# RasPi7021.net
KiCad netlist of a schematic drawn in EAGLE
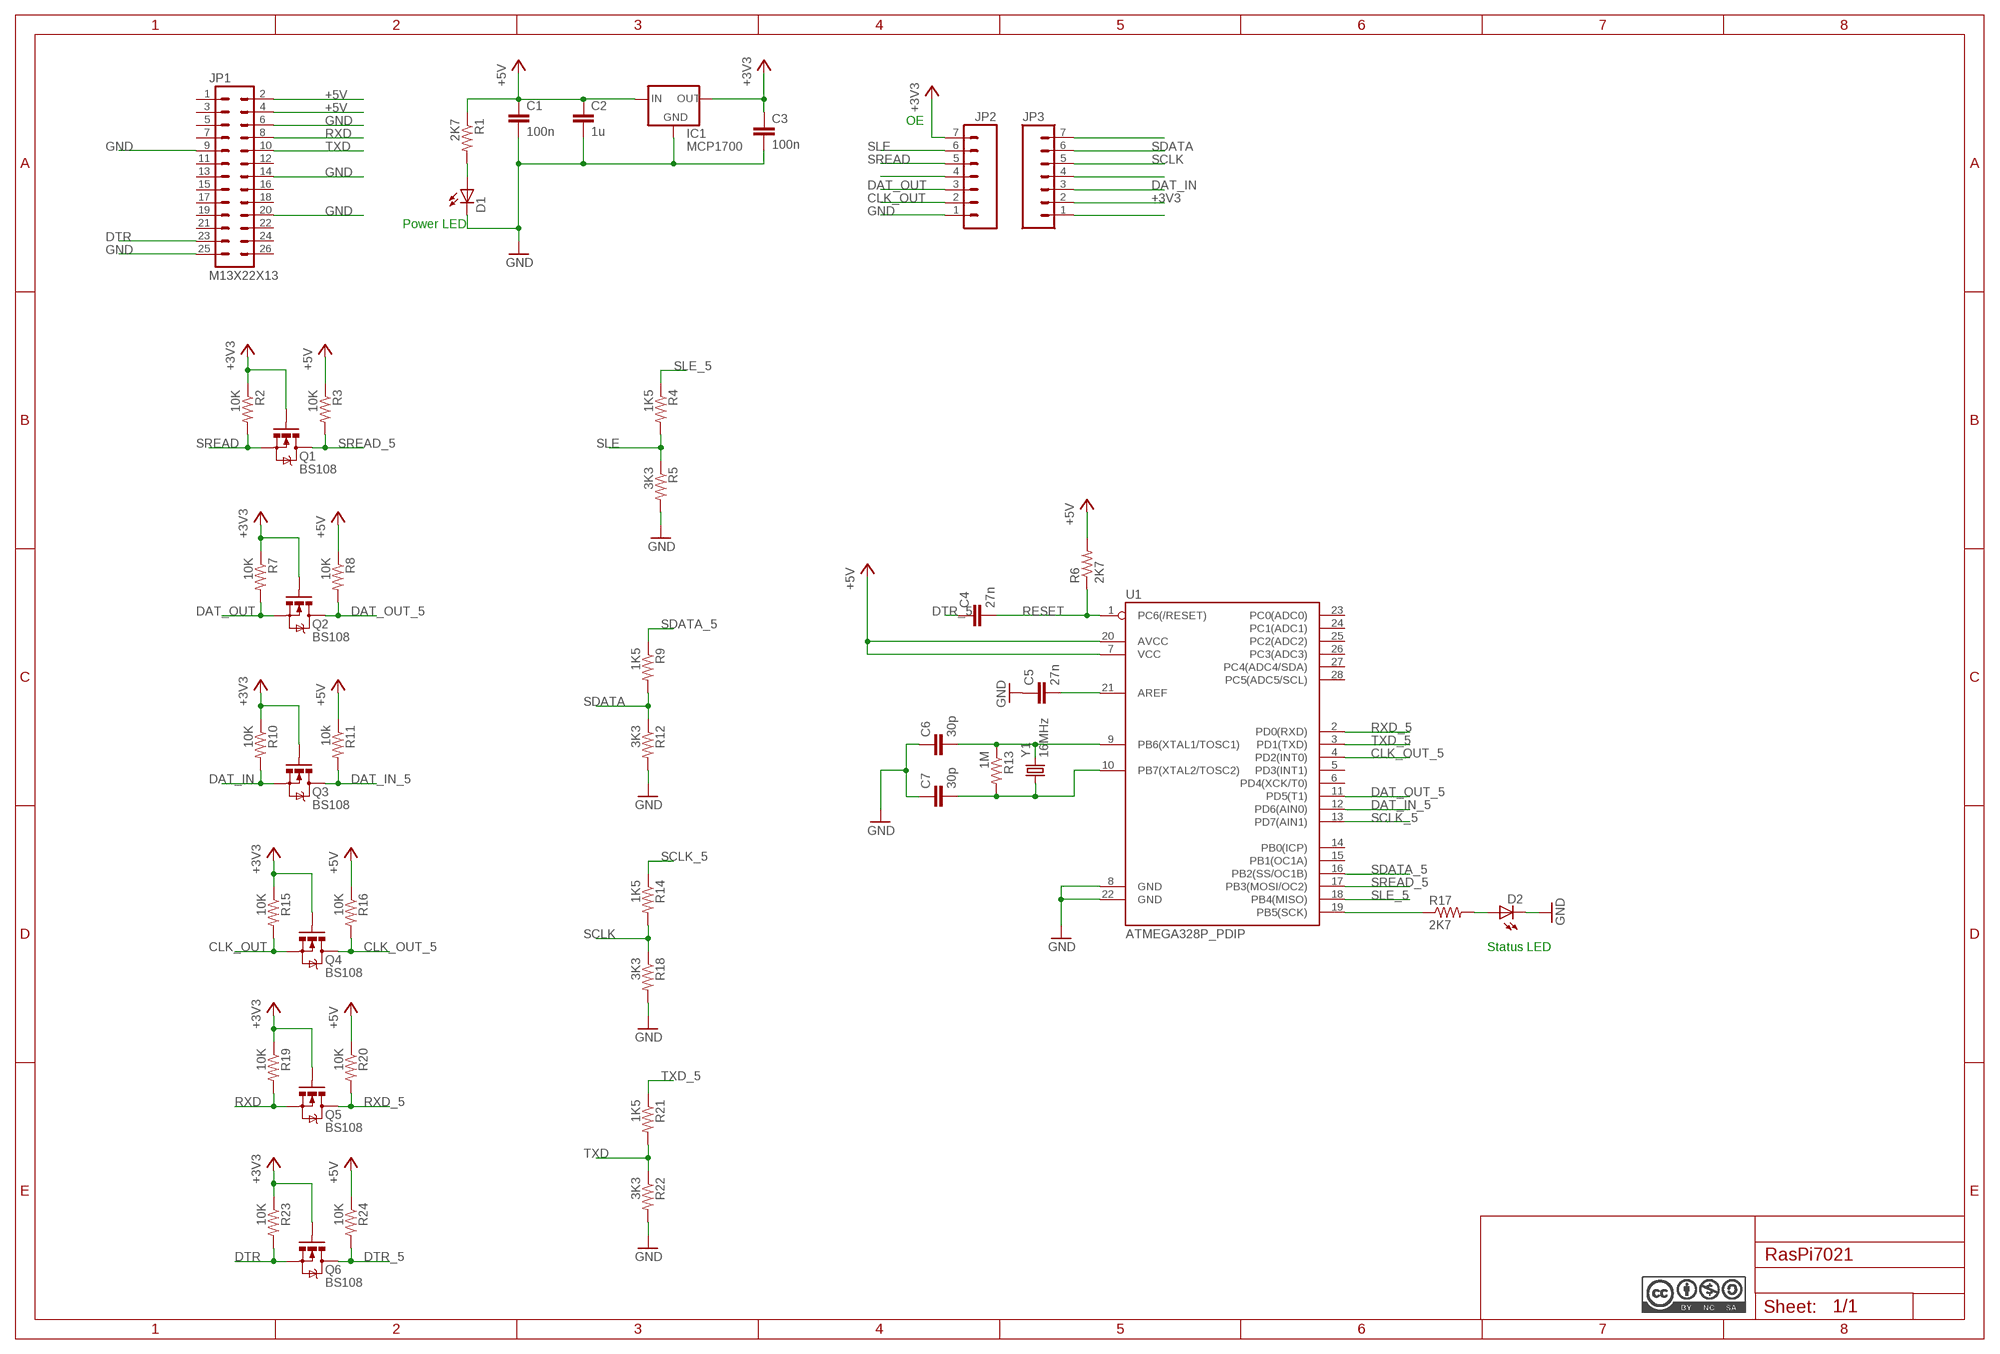
[diagram p0: schematic, sheet 1]

(export (version "E")
  (design (tool "Eeschema 10.0.6"))
  (components
    (comp (ref "C1")
      (value "100n")
      (footprint "eagle-import:CAP-PTH-SMALLEZ")
      (libsource (lib "eagle-import") (part "CAPEZ"))
    )
    (comp (ref "C2")
      (value "1u")
      (footprint "eagle-import:CAP-PTH-SMALLEZ")
      (libsource (lib "eagle-import") (part "CAPEZ"))
    )
    (comp (ref "C3")
      (value "100n")
      (footprint "eagle-import:CAP-PTH-SMALLEZ")
      (libsource (lib "eagle-import") (part "CAPEZ"))
    )
    (comp (ref "C4")
      (value "27n")
      (footprint "eagle-import:CAP-PTH-SMALLEZ")
      (libsource (lib "eagle-import") (part "CAPEZ"))
    )
    (comp (ref "C5")
      (value "27n")
      (footprint "eagle-import:CAP-PTH-SMALLEZ")
      (libsource (lib "eagle-import") (part "CAPEZ"))
    )
    (comp (ref "C6")
      (value "30p")
      (footprint "eagle-import:CAP-PTH-SMALLEZ")
      (libsource (lib "eagle-import") (part "CAPEZ"))
    )
    (comp (ref "C7")
      (value "30p")
      (footprint "eagle-import:CAP-PTH-SMALLEZ")
      (libsource (lib "eagle-import") (part "CAPEZ"))
    )
    (comp (ref "D1")
      (value "LED3MM")
      (footprint "eagle-import:LED3MM")
      (libsource (lib "eagle-import") (part "LED3MM"))
    )
    (comp (ref "D2")
      (value "LED3MM")
      (footprint "eagle-import:LED3MM")
      (libsource (lib "eagle-import") (part "LED3MM"))
    )
    (comp (ref "IC1")
      (value "MCP1700")
      (footprint "eagle-import:TO92-INLINE")
      (libsource (lib "eagle-import") (part "MCP1700INLINE"))
    )
    (comp (ref "JP1")
      (value "M13X22X13")
      (footprint "eagle-import:2X13")
      (libsource (lib "eagle-import") (part "M13X22X13"))
    )
    (comp (ref "JP2")
      (value "M07")
      (footprint "eagle-import:1X07")
      (libsource (lib "eagle-import") (part "M07"))
    )
    (comp (ref "JP3")
      (value "M07")
      (footprint "eagle-import:1X07")
      (libsource (lib "eagle-import") (part "M07"))
    )
    (comp (ref "Q1")
      (value "BS108")
      (footprint "eagle-import:TO-92")
      (libsource (lib "eagle-import") (part "MOSFET-NCHANNELBS170"))
    )
    (comp (ref "Q2")
      (value "BS108")
      (footprint "eagle-import:TO-92")
      (libsource (lib "eagle-import") (part "MOSFET-NCHANNELBS170"))
    )
    (comp (ref "Q3")
      (value "BS108")
      (footprint "eagle-import:TO-92")
      (libsource (lib "eagle-import") (part "MOSFET-NCHANNELBS170"))
    )
    (comp (ref "Q4")
      (value "BS108")
      (footprint "eagle-import:TO-92")
      (libsource (lib "eagle-import") (part "MOSFET-NCHANNELBS170"))
    )
    (comp (ref "Q5")
      (value "BS108")
      (footprint "eagle-import:TO-92")
      (libsource (lib "eagle-import") (part "MOSFET-NCHANNELBS170"))
    )
    (comp (ref "Q6")
      (value "BS108")
      (footprint "eagle-import:TO-92")
      (libsource (lib "eagle-import") (part "MOSFET-NCHANNELBS170"))
    )
    (comp (ref "R1")
      (value "2K7")
      (footprint "eagle-import:AXIAL-0.3EZ")
      (libsource (lib "eagle-import") (part "RESISTOREZ"))
    )
    (comp (ref "R2")
      (value "10K")
      (footprint "eagle-import:AXIAL-0.3EZ")
      (libsource (lib "eagle-import") (part "RESISTOREZ"))
    )
    (comp (ref "R3")
      (value "10K")
      (footprint "eagle-import:AXIAL-0.3EZ")
      (libsource (lib "eagle-import") (part "RESISTOREZ"))
    )
    (comp (ref "R4")
      (value "1K5")
      (footprint "eagle-import:AXIAL-0.3EZ")
      (libsource (lib "eagle-import") (part "RESISTOREZ"))
    )
    (comp (ref "R5")
      (value "3K3")
      (footprint "eagle-import:AXIAL-0.3EZ")
      (libsource (lib "eagle-import") (part "RESISTOREZ"))
    )
    (comp (ref "R6")
      (value "2K7")
      (footprint "eagle-import:AXIAL-0.3EZ")
      (libsource (lib "eagle-import") (part "RESISTOREZ"))
    )
    (comp (ref "R7")
      (value "10K")
      (footprint "eagle-import:AXIAL-0.3EZ")
      (libsource (lib "eagle-import") (part "RESISTOREZ"))
    )
    (comp (ref "R8")
      (value "10K")
      (footprint "eagle-import:AXIAL-0.3EZ")
      (libsource (lib "eagle-import") (part "RESISTOREZ"))
    )
    (comp (ref "R9")
      (value "1K5")
      (footprint "eagle-import:AXIAL-0.3EZ")
      (libsource (lib "eagle-import") (part "RESISTOREZ"))
    )
    (comp (ref "R10")
      (value "10K")
      (footprint "eagle-import:AXIAL-0.3EZ")
      (libsource (lib "eagle-import") (part "RESISTOREZ"))
    )
    (comp (ref "R11")
      (value "10k")
      (footprint "eagle-import:AXIAL-0.3EZ")
      (libsource (lib "eagle-import") (part "RESISTOREZ"))
    )
    (comp (ref "R12")
      (value "3K3")
      (footprint "eagle-import:AXIAL-0.3EZ")
      (libsource (lib "eagle-import") (part "RESISTOREZ"))
    )
    (comp (ref "R13")
      (value "1M")
      (footprint "eagle-import:AXIAL-0.3EZ")
      (libsource (lib "eagle-import") (part "RESISTOREZ"))
    )
    (comp (ref "R14")
      (value "1K5")
      (footprint "eagle-import:AXIAL-0.3EZ")
      (libsource (lib "eagle-import") (part "RESISTOREZ"))
    )
    (comp (ref "R15")
      (value "10K")
      (footprint "eagle-import:AXIAL-0.3EZ")
      (libsource (lib "eagle-import") (part "RESISTOREZ"))
    )
    (comp (ref "R16")
      (value "10K")
      (footprint "eagle-import:AXIAL-0.3EZ")
      (libsource (lib "eagle-import") (part "RESISTOREZ"))
    )
    (comp (ref "R17")
      (value "2K7")
      (footprint "eagle-import:AXIAL-0.3EZ")
      (libsource (lib "eagle-import") (part "RESISTOREZ"))
    )
    (comp (ref "R18")
      (value "3K3")
      (footprint "eagle-import:AXIAL-0.3EZ")
      (libsource (lib "eagle-import") (part "RESISTOREZ"))
    )
    (comp (ref "R19")
      (value "10K")
      (footprint "eagle-import:AXIAL-0.3EZ")
      (libsource (lib "eagle-import") (part "RESISTOREZ"))
    )
    (comp (ref "R20")
      (value "10K")
      (footprint "eagle-import:AXIAL-0.3EZ")
      (libsource (lib "eagle-import") (part "RESISTOREZ"))
    )
    (comp (ref "R21")
      (value "1K5")
      (footprint "eagle-import:AXIAL-0.3EZ")
      (libsource (lib "eagle-import") (part "RESISTOREZ"))
    )
    (comp (ref "R22")
      (value "3K3")
      (footprint "eagle-import:AXIAL-0.3EZ")
      (libsource (lib "eagle-import") (part "RESISTOREZ"))
    )
    (comp (ref "R23")
      (value "10K")
      (footprint "eagle-import:AXIAL-0.3EZ")
      (libsource (lib "eagle-import") (part "RESISTOREZ"))
    )
    (comp (ref "R24")
      (value "10K")
      (footprint "eagle-import:AXIAL-0.3EZ")
      (libsource (lib "eagle-import") (part "RESISTOREZ"))
    )
    (comp (ref "U1")
      (value "ATMEGA328P_PDIP")
      (footprint "eagle-import:DIL28-3")
      (libsource (lib "eagle-import") (part "ATMEGA328P_PDIP"))
    )
    (comp (ref "Y1")
      (value "16MHz")
      (footprint "eagle-import:CRYSTAL_HC49_S")
      (libsource (lib "eagle-import") (part "CRYSTAL_CRYSTALHC49S"))
    )
  )
  (nets
    (net (code "1") (name "+3V3") (class "Default")
      (node (ref "C3") (pin "1") (pinfunction "1_1") (pintype "passive"))
      (node (ref "IC1") (pin "3") (pinfunction "OUT_3") (pintype "passive"))
      (node (ref "JP2") (pin "7") (pinfunction "7_7") (pintype "passive"))
      (node (ref "JP3") (pin "2") (pinfunction "2_2") (pintype "passive"))
      (node (ref "Q1") (pin "2") (pinfunction "G_2") (pintype "passive"))
      (node (ref "Q2") (pin "2") (pinfunction "G_2") (pintype "passive"))
      (node (ref "Q3") (pin "2") (pinfunction "G_2") (pintype "passive"))
      (node (ref "Q4") (pin "2") (pinfunction "G_2") (pintype "passive"))
      (node (ref "Q5") (pin "2") (pinfunction "G_2") (pintype "passive"))
      (node (ref "Q6") (pin "2") (pinfunction "G_2") (pintype "passive"))
      (node (ref "R10") (pin "P$1") (pinfunction "1_P$1") (pintype "passive"))
      (node (ref "R15") (pin "P$1") (pinfunction "1_P$1") (pintype "passive"))
      (node (ref "R19") (pin "P$1") (pinfunction "1_P$1") (pintype "passive"))
      (node (ref "R2") (pin "P$1") (pinfunction "1_P$1") (pintype "passive"))
      (node (ref "R23") (pin "P$1") (pinfunction "1_P$1") (pintype "passive"))
      (node (ref "R7") (pin "P$1") (pinfunction "1_P$1") (pintype "passive"))
    )
    (net (code "2") (name "+5V") (class "Default")
      (node (ref "C1") (pin "1") (pinfunction "1_1") (pintype "passive"))
      (node (ref "C2") (pin "1") (pinfunction "1_1") (pintype "passive"))
      (node (ref "IC1") (pin "2") (pinfunction "IN_2") (pintype "input"))
      (node (ref "JP1") (pin "2") (pinfunction "2_2") (pintype "passive"))
      (node (ref "JP1") (pin "4") (pinfunction "4_4") (pintype "passive"))
      (node (ref "R1") (pin "P$1") (pinfunction "1_P$1") (pintype "passive"))
      (node (ref "R11") (pin "P$1") (pinfunction "1_P$1") (pintype "passive"))
      (node (ref "R16") (pin "P$1") (pinfunction "1_P$1") (pintype "passive"))
      (node (ref "R20") (pin "P$1") (pinfunction "1_P$1") (pintype "passive"))
      (node (ref "R24") (pin "P$1") (pinfunction "1_P$1") (pintype "passive"))
      (node (ref "R3") (pin "P$1") (pinfunction "1_P$1") (pintype "passive"))
      (node (ref "R6") (pin "P$2") (pinfunction "2_P$2") (pintype "passive"))
      (node (ref "R8") (pin "P$1") (pinfunction "1_P$1") (pintype "passive"))
      (node (ref "U1") (pin "20") (pinfunction "AVCC_20") (pintype "bidirectional"))
      (node (ref "U1") (pin "7") (pinfunction "VCC_7") (pintype "bidirectional"))
    )
    (net (code "3") (name "/CLK_OUT") (class "Default")
      (node (ref "JP2") (pin "2") (pinfunction "2_2") (pintype "passive"))
      (node (ref "Q4") (pin "3") (pinfunction "S_3") (pintype "passive"))
      (node (ref "R15") (pin "P$2") (pinfunction "2_P$2") (pintype "passive"))
    )
    (net (code "4") (name "/CLK_OUT_5") (class "Default")
      (node (ref "Q4") (pin "1") (pinfunction "D_1") (pintype "passive"))
      (node (ref "R16") (pin "P$2") (pinfunction "2_P$2") (pintype "passive"))
      (node (ref "U1") (pin "4") (pinfunction "PD2(INT0)_4") (pintype "bidirectional"))
    )
    (net (code "5") (name "/DAT_IN") (class "Default")
      (node (ref "JP3") (pin "3") (pinfunction "3_3") (pintype "passive"))
      (node (ref "Q3") (pin "3") (pinfunction "S_3") (pintype "passive"))
      (node (ref "R10") (pin "P$2") (pinfunction "2_P$2") (pintype "passive"))
    )
    (net (code "6") (name "/DAT_IN_5") (class "Default")
      (node (ref "Q3") (pin "1") (pinfunction "D_1") (pintype "passive"))
      (node (ref "R11") (pin "P$2") (pinfunction "2_P$2") (pintype "passive"))
      (node (ref "U1") (pin "12") (pinfunction "PD6(AIN0)_12") (pintype "bidirectional"))
    )
    (net (code "7") (name "/DAT_OUT") (class "Default")
      (node (ref "JP2") (pin "3") (pinfunction "3_3") (pintype "passive"))
      (node (ref "Q2") (pin "3") (pinfunction "S_3") (pintype "passive"))
      (node (ref "R7") (pin "P$2") (pinfunction "2_P$2") (pintype "passive"))
    )
    (net (code "8") (name "/DAT_OUT_5") (class "Default")
      (node (ref "Q2") (pin "1") (pinfunction "D_1") (pintype "passive"))
      (node (ref "R8") (pin "P$2") (pinfunction "2_P$2") (pintype "passive"))
      (node (ref "U1") (pin "11") (pinfunction "PD5(T1)_11") (pintype "bidirectional"))
    )
    (net (code "9") (name "/DTR") (class "Default")
      (node (ref "JP1") (pin "23") (pinfunction "23_23") (pintype "passive"))
      (node (ref "Q6") (pin "3") (pinfunction "S_3") (pintype "passive"))
      (node (ref "R23") (pin "P$2") (pinfunction "2_P$2") (pintype "passive"))
    )
    (net (code "10") (name "/DTR_5") (class "Default")
      (node (ref "C4") (pin "1") (pinfunction "1_1") (pintype "passive"))
      (node (ref "Q6") (pin "1") (pinfunction "D_1") (pintype "passive"))
      (node (ref "R24") (pin "P$2") (pinfunction "2_P$2") (pintype "passive"))
    )
    (net (code "11") (name "/RESET") (class "Default")
      (node (ref "C4") (pin "2") (pinfunction "2_2") (pintype "passive"))
      (node (ref "R6") (pin "P$1") (pinfunction "1_P$1") (pintype "passive"))
      (node (ref "U1") (pin "1") (pinfunction "PC6(/RESET)_1") (pintype "bidirectional"))
    )
    (net (code "12") (name "/RXD") (class "Default")
      (node (ref "JP1") (pin "8") (pinfunction "8_8") (pintype "passive"))
      (node (ref "Q5") (pin "3") (pinfunction "S_3") (pintype "passive"))
      (node (ref "R19") (pin "P$2") (pinfunction "2_P$2") (pintype "passive"))
    )
    (net (code "13") (name "/RXD_5") (class "Default")
      (node (ref "Q5") (pin "1") (pinfunction "D_1") (pintype "passive"))
      (node (ref "R20") (pin "P$2") (pinfunction "2_P$2") (pintype "passive"))
      (node (ref "U1") (pin "2") (pinfunction "PD0(RXD)_2") (pintype "bidirectional"))
    )
    (net (code "14") (name "/SCLK") (class "Default")
      (node (ref "JP3") (pin "5") (pinfunction "5_5") (pintype "passive"))
      (node (ref "R14") (pin "P$2") (pinfunction "2_P$2") (pintype "passive"))
      (node (ref "R18") (pin "P$1") (pinfunction "1_P$1") (pintype "passive"))
    )
    (net (code "15") (name "/SCLK_5") (class "Default")
      (node (ref "R14") (pin "P$1") (pinfunction "1_P$1") (pintype "passive"))
      (node (ref "U1") (pin "13") (pinfunction "PD7(AIN1)_13") (pintype "bidirectional"))
    )
    (net (code "16") (name "/SDATA") (class "Default")
      (node (ref "JP3") (pin "6") (pinfunction "6_6") (pintype "passive"))
      (node (ref "R12") (pin "P$1") (pinfunction "1_P$1") (pintype "passive"))
      (node (ref "R9") (pin "P$2") (pinfunction "2_P$2") (pintype "passive"))
    )
    (net (code "17") (name "/SDATA_5") (class "Default")
      (node (ref "R9") (pin "P$1") (pinfunction "1_P$1") (pintype "passive"))
      (node (ref "U1") (pin "16") (pinfunction "PB2(SS/OC1B)_16") (pintype "bidirectional"))
    )
    (net (code "18") (name "/SLE") (class "Default")
      (node (ref "JP2") (pin "6") (pinfunction "6_6") (pintype "passive"))
      (node (ref "R4") (pin "P$2") (pinfunction "2_P$2") (pintype "passive"))
      (node (ref "R5") (pin "P$1") (pinfunction "1_P$1") (pintype "passive"))
    )
    (net (code "19") (name "/SLE_5") (class "Default")
      (node (ref "R4") (pin "P$1") (pinfunction "1_P$1") (pintype "passive"))
      (node (ref "U1") (pin "18") (pinfunction "PB4(MISO)_18") (pintype "bidirectional"))
    )
    (net (code "20") (name "/SREAD") (class "Default")
      (node (ref "JP2") (pin "5") (pinfunction "5_5") (pintype "passive"))
      (node (ref "Q1") (pin "3") (pinfunction "S_3") (pintype "passive"))
      (node (ref "R2") (pin "P$2") (pinfunction "2_P$2") (pintype "passive"))
    )
    (net (code "21") (name "/SREAD_5") (class "Default")
      (node (ref "Q1") (pin "1") (pinfunction "D_1") (pintype "passive"))
      (node (ref "R3") (pin "P$2") (pinfunction "2_P$2") (pintype "passive"))
      (node (ref "U1") (pin "17") (pinfunction "PB3(MOSI/OC2)_17") (pintype "bidirectional"))
    )
    (net (code "22") (name "/TXD") (class "Default")
      (node (ref "JP1") (pin "10") (pinfunction "10_10") (pintype "passive"))
      (node (ref "R21") (pin "P$2") (pinfunction "2_P$2") (pintype "passive"))
      (node (ref "R22") (pin "P$1") (pinfunction "1_P$1") (pintype "passive"))
    )
    (net (code "23") (name "/TXD_5") (class "Default")
      (node (ref "R21") (pin "P$1") (pinfunction "1_P$1") (pintype "passive"))
      (node (ref "U1") (pin "3") (pinfunction "PD1(TXD)_3") (pintype "bidirectional"))
    )
    (net (code "24") (name "GND") (class "Default")
      (node (ref "C1") (pin "2") (pinfunction "2_2") (pintype "passive"))
      (node (ref "C2") (pin "2") (pinfunction "2_2") (pintype "passive"))
      (node (ref "C3") (pin "2") (pinfunction "2_2") (pintype "passive"))
      (node (ref "C5") (pin "1") (pinfunction "1_1") (pintype "passive"))
      (node (ref "C6") (pin "1") (pinfunction "1_1") (pintype "passive"))
      (node (ref "C7") (pin "1") (pinfunction "1_1") (pintype "passive"))
      (node (ref "D1") (pin "K") (pinfunction "C_K") (pintype "passive"))
      (node (ref "D2") (pin "K") (pinfunction "C_K") (pintype "passive"))
      (node (ref "IC1") (pin "1") (pinfunction "GND_1") (pintype "input"))
      (node (ref "JP1") (pin "14") (pinfunction "14_14") (pintype "passive"))
      (node (ref "JP1") (pin "20") (pinfunction "20_20") (pintype "passive"))
      (node (ref "JP1") (pin "25") (pinfunction "25_25") (pintype "passive"))
      (node (ref "JP1") (pin "6") (pinfunction "6_6") (pintype "passive"))
      (node (ref "JP1") (pin "9") (pinfunction "9_9") (pintype "passive"))
      (node (ref "JP2") (pin "1") (pinfunction "1_1") (pintype "passive"))
      (node (ref "R12") (pin "P$2") (pinfunction "2_P$2") (pintype "passive"))
      (node (ref "R18") (pin "P$2") (pinfunction "2_P$2") (pintype "passive"))
      (node (ref "R22") (pin "P$2") (pinfunction "2_P$2") (pintype "passive"))
      (node (ref "R5") (pin "P$2") (pinfunction "2_P$2") (pintype "passive"))
      (node (ref "U1") (pin "22") (pinfunction "GND_22") (pintype "bidirectional"))
      (node (ref "U1") (pin "8") (pinfunction "GND_8") (pintype "bidirectional"))
    )
    (net (code "25") (name "Net-(R1-2)") (class "Default")
      (node (ref "D1") (pin "A") (pinfunction "A_A") (pintype "passive"))
      (node (ref "R1") (pin "P$2") (pinfunction "2_P$2") (pintype "passive"))
    )
    (net (code "26") (name "Net-(R13-1)") (class "Default")
      (node (ref "C6") (pin "2") (pinfunction "2_2") (pintype "passive"))
      (node (ref "R13") (pin "P$1") (pinfunction "1_P$1") (pintype "passive"))
      (node (ref "U1") (pin "9") (pinfunction "PB6(XTAL1/TOSC1)_9") (pintype "bidirectional"))
      (node (ref "Y1") (pin "2") (pinfunction "2_2") (pintype "passive"))
    )
    (net (code "27") (name "Net-(R13-2)") (class "Default")
      (node (ref "C7") (pin "2") (pinfunction "2_2") (pintype "passive"))
      (node (ref "R13") (pin "P$2") (pinfunction "2_P$2") (pintype "passive"))
      (node (ref "U1") (pin "10") (pinfunction "PB7(XTAL2/TOSC2)_10") (pintype "bidirectional"))
      (node (ref "Y1") (pin "1") (pinfunction "1_1") (pintype "passive"))
    )
    (net (code "28") (name "Net-(R17-1)") (class "Default")
      (node (ref "R17") (pin "P$1") (pinfunction "1_P$1") (pintype "passive"))
      (node (ref "U1") (pin "19") (pinfunction "PB5(SCK)_19") (pintype "bidirectional"))
    )
    (net (code "29") (name "Net-(R17-2)") (class "Default")
      (node (ref "D2") (pin "A") (pinfunction "A_A") (pintype "passive"))
      (node (ref "R17") (pin "P$2") (pinfunction "2_P$2") (pintype "passive"))
    )
    (net (code "30") (name "Net-(U1-AREF)") (class "Default")
      (node (ref "C5") (pin "2") (pinfunction "2_2") (pintype "passive"))
      (node (ref "U1") (pin "21") (pinfunction "AREF_21") (pintype "bidirectional"))
    )
    (net (code "31") (name "unconnected-(JP1-Pad1)") (class "Default")
      (node (ref "JP1") (pin "1") (pinfunction "1_1") (pintype "passive"))
    )
    (net (code "32") (name "unconnected-(JP1-Pad3)") (class "Default")
      (node (ref "JP1") (pin "3") (pinfunction "3_3") (pintype "passive"))
    )
    (net (code "33") (name "unconnected-(JP1-Pad5)") (class "Default")
      (node (ref "JP1") (pin "5") (pinfunction "5_5") (pintype "passive"))
    )
    (net (code "34") (name "unconnected-(JP1-Pad7)") (class "Default")
      (node (ref "JP1") (pin "7") (pinfunction "7_7") (pintype "passive"))
    )
    (net (code "35") (name "unconnected-(JP1-Pad11)") (class "Default")
      (node (ref "JP1") (pin "11") (pinfunction "11_11") (pintype "passive"))
    )
    (net (code "36") (name "unconnected-(JP1-Pad12)") (class "Default")
      (node (ref "JP1") (pin "12") (pinfunction "12_12") (pintype "passive"))
    )
    (net (code "37") (name "unconnected-(JP1-Pad13)") (class "Default")
      (node (ref "JP1") (pin "13") (pinfunction "13_13") (pintype "passive"))
    )
    (net (code "38") (name "unconnected-(JP1-Pad15)") (class "Default")
      (node (ref "JP1") (pin "15") (pinfunction "15_15") (pintype "passive"))
    )
    (net (code "39") (name "unconnected-(JP1-Pad16)") (class "Default")
      (node (ref "JP1") (pin "16") (pinfunction "16_16") (pintype "passive"))
    )
    (net (code "40") (name "unconnected-(JP1-Pad17)") (class "Default")
      (node (ref "JP1") (pin "17") (pinfunction "17_17") (pintype "passive"))
    )
    (net (code "41") (name "unconnected-(JP1-Pad18)") (class "Default")
      (node (ref "JP1") (pin "18") (pinfunction "18_18") (pintype "passive"))
    )
    (net (code "42") (name "unconnected-(JP1-Pad19)") (class "Default")
      (node (ref "JP1") (pin "19") (pinfunction "19_19") (pintype "passive"))
    )
    (net (code "43") (name "unconnected-(JP1-Pad21)") (class "Default")
      (node (ref "JP1") (pin "21") (pinfunction "21_21") (pintype "passive"))
    )
    (net (code "44") (name "unconnected-(JP1-Pad22)") (class "Default")
      (node (ref "JP1") (pin "22") (pinfunction "22_22") (pintype "passive"))
    )
    (net (code "45") (name "unconnected-(JP1-Pad24)") (class "Default")
      (node (ref "JP1") (pin "24") (pinfunction "24_24") (pintype "passive"))
    )
    (net (code "46") (name "unconnected-(JP1-Pad26)") (class "Default")
      (node (ref "JP1") (pin "26") (pinfunction "26_26") (pintype "passive"))
    )
    (net (code "47") (name "unconnected-(JP2-Pad4)") (class "Default")
      (node (ref "JP2") (pin "4") (pinfunction "4_4") (pintype "passive"))
    )
    (net (code "48") (name "unconnected-(JP3-Pad1)") (class "Default")
      (node (ref "JP3") (pin "1") (pinfunction "1_1") (pintype "passive"))
    )
    (net (code "49") (name "unconnected-(JP3-Pad4)") (class "Default")
      (node (ref "JP3") (pin "4") (pinfunction "4_4") (pintype "passive"))
    )
    (net (code "50") (name "unconnected-(JP3-Pad7)") (class "Default")
      (node (ref "JP3") (pin "7") (pinfunction "7_7") (pintype "passive"))
    )
    (net (code "51") (name "unconnected-(U1-PB0(ICP)-Pad14)") (class "Default")
      (node (ref "U1") (pin "14") (pinfunction "PB0(ICP)_14") (pintype "bidirectional"))
    )
    (net (code "52") (name "unconnected-(U1-PB1(OC1A)-Pad15)") (class "Default")
      (node (ref "U1") (pin "15") (pinfunction "PB1(OC1A)_15") (pintype "bidirectional"))
    )
    (net (code "53") (name "unconnected-(U1-PC0(ADC0)-Pad23)") (class "Default")
      (node (ref "U1") (pin "23") (pinfunction "PC0(ADC0)_23") (pintype "bidirectional"))
    )
    (net (code "54") (name "unconnected-(U1-PC1(ADC1)-Pad24)") (class "Default")
      (node (ref "U1") (pin "24") (pinfunction "PC1(ADC1)_24") (pintype "bidirectional"))
    )
    (net (code "55") (name "unconnected-(U1-PC2(ADC2)-Pad25)") (class "Default")
      (node (ref "U1") (pin "25") (pinfunction "PC2(ADC2)_25") (pintype "bidirectional"))
    )
    (net (code "56") (name "unconnected-(U1-PC3(ADC3)-Pad26)") (class "Default")
      (node (ref "U1") (pin "26") (pinfunction "PC3(ADC3)_26") (pintype "bidirectional"))
    )
    (net (code "57") (name "unconnected-(U1-PC4(ADC4{slash}SDA)-Pad27)") (class "Default")
      (node (ref "U1") (pin "27") (pinfunction "PC4(ADC4/SDA)_27") (pintype "bidirectional"))
    )
    (net (code "58") (name "unconnected-(U1-PC5(ADC5{slash}SCL)-Pad28)") (class "Default")
      (node (ref "U1") (pin "28") (pinfunction "PC5(ADC5/SCL)_28") (pintype "bidirectional"))
    )
    (net (code "59") (name "unconnected-(U1-PD3(INT1)-Pad5)") (class "Default")
      (node (ref "U1") (pin "5") (pinfunction "PD3(INT1)_5") (pintype "bidirectional"))
    )
    (net (code "60") (name "unconnected-(U1-PD4(XCK{slash}T0)-Pad6)") (class "Default")
      (node (ref "U1") (pin "6") (pinfunction "PD4(XCK/T0)_6") (pintype "bidirectional"))
    )
  )
)
